# Motors.net
KiCad netlist of a schematic drawn in Altium Designer
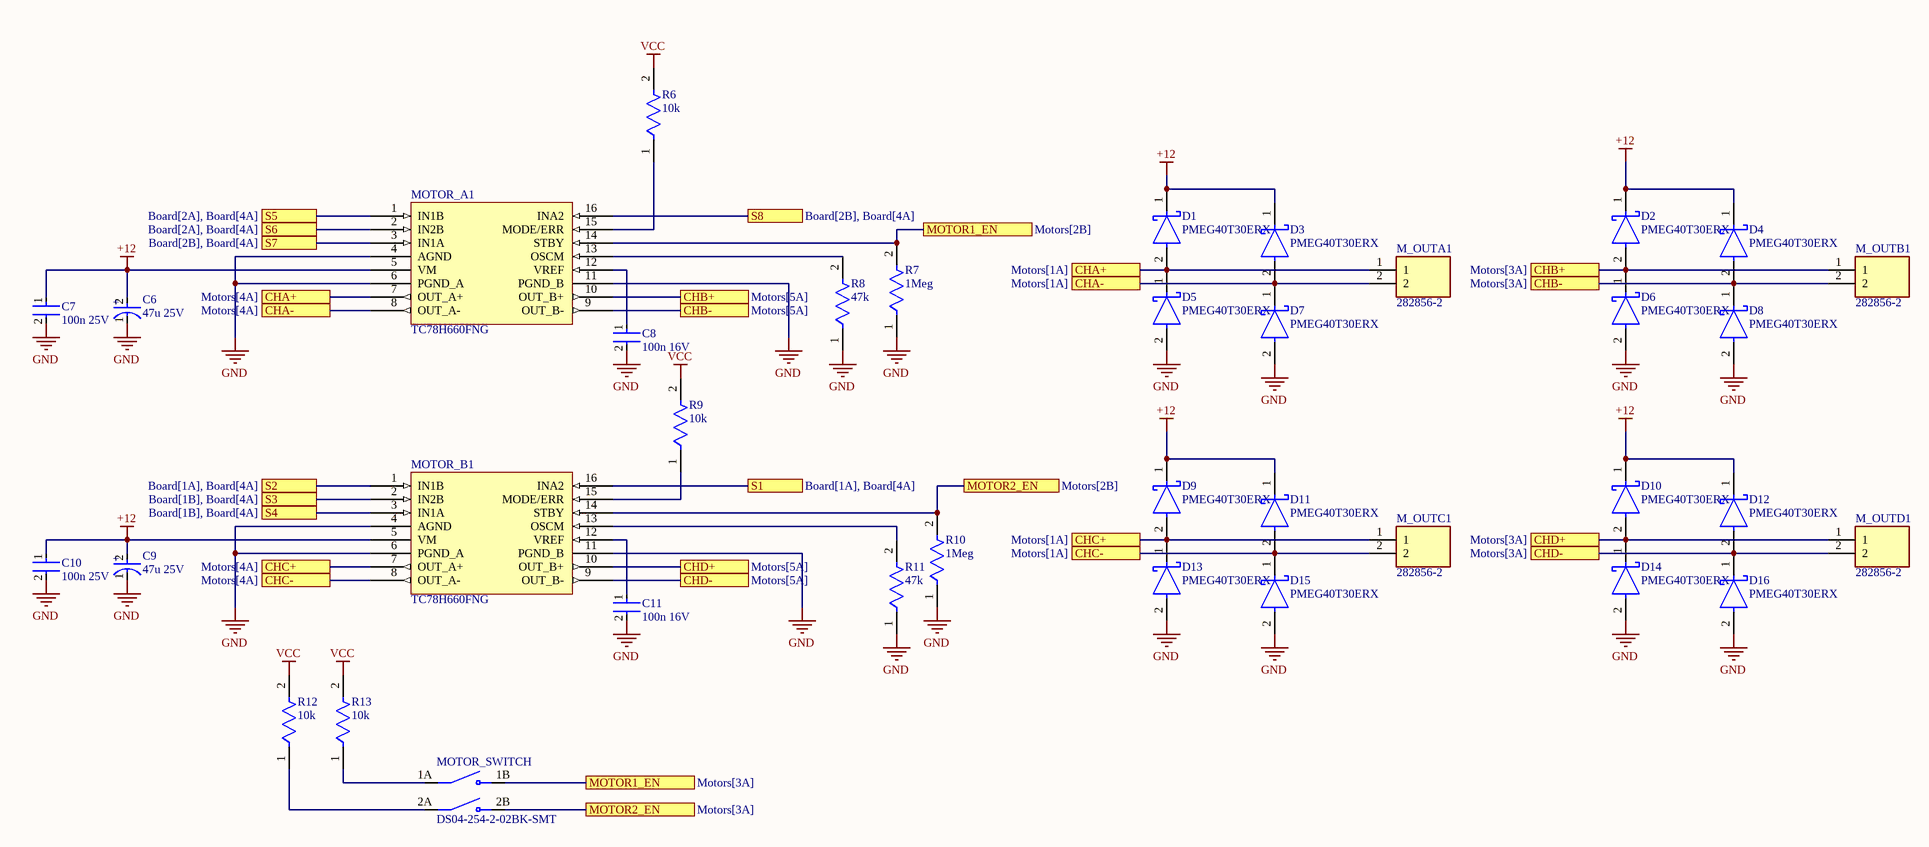
[diagram p0: Motors.SchDoc]

(export (version "E")
  (design (tool "Eeschema 10.0.6"))
  (components
    (comp (ref "C6")
      (value "47u 25V")
      (footprint "FP-T491D476K025AT-MFG")
      (description "CAP TANT 47UF 10% 25V 2917")
      (fields (field (name "VOLTAGE") "25V") (field (name "TOLERANCE") "10%"))
      (libsource (lib "Altium Content Vault") (part "203bc49f2ac43e59fd269a8c329ed05"))
    )
    (comp (ref "C7")
      (value "100n 25V")
      (footprint "FP-C0402-BB-MFG")
      (description "CAP CER 0.1UF 16V X7R 0402")
      (fields
        (field (name "TOLERANCE") "0.1")
        (field (name "OCTOPART") "https://octopart.com/c0402c104k4ractu-kemet-94158")
      )
      (libsource (lib "Altium Content Vault") (part "b4654b650e69147ec39a6b967a45e02"))
    )
    (comp (ref "C8")
      (value "100n 16V")
      (footprint "FP-C0402-BB-MFG")
      (description "CAP CER 0.1UF 16V X7R 0402")
      (fields
        (field (name "TOLERANCE") "0.1")
        (field (name "OCTOPART") "https://octopart.com/c0402c104k4ractu-kemet-94158")
      )
      (libsource (lib "Altium Content Vault") (part "b4654b650e69147ec39a6b967a45e02"))
    )
    (comp (ref "C9")
      (value "47u 25V")
      (footprint "FP-T491D476K025AT-MFG")
      (description "CAP TANT 47UF 10% 25V 2917")
      (fields (field (name "VOLTAGE") "25V") (field (name "TOLERANCE") "10%"))
      (libsource (lib "Altium Content Vault") (part "203bc49f2ac43e59fd269a8c329ed05"))
    )
    (comp (ref "C10")
      (value "100n 25V")
      (footprint "FP-C0402-BB-MFG")
      (description "CAP CER 0.1UF 16V X7R 0402")
      (fields
        (field (name "TOLERANCE") "0.1")
        (field (name "OCTOPART") "https://octopart.com/c0402c104k4ractu-kemet-94158")
      )
      (libsource (lib "Altium Content Vault") (part "b4654b650e69147ec39a6b967a45e02"))
    )
    (comp (ref "C11")
      (value "100n 16V")
      (footprint "FP-C0402-BB-MFG")
      (description "CAP CER 0.1UF 16V X7R 0402")
      (fields
        (field (name "TOLERANCE") "0.1")
        (field (name "OCTOPART") "https://octopart.com/c0402c104k4ractu-kemet-94158")
      )
      (libsource (lib "Altium Content Vault") (part "b4654b650e69147ec39a6b967a45e02"))
    )
    (comp (ref "D1")
      (value "PMEG40T30ERX")
      (footprint "FP-SOD123-IPC_A")
      (description "DIODE SCHOTTKY 40V 1A SOD123")
      (libsource (lib "Altium Content Vault") (part "1d6ec82d83fb6aee721767c19dac4b9"))
    )
    (comp (ref "D2")
      (value "PMEG40T30ERX")
      (footprint "FP-SOD123-IPC_A")
      (description "DIODE SCHOTTKY 40V 1A SOD123")
      (libsource (lib "Altium Content Vault") (part "1d6ec82d83fb6aee721767c19dac4b9"))
    )
    (comp (ref "D3")
      (value "PMEG40T30ERX")
      (footprint "FP-SOD123-IPC_A")
      (description "DIODE SCHOTTKY 40V 1A SOD123")
      (libsource (lib "Altium Content Vault") (part "1d6ec82d83fb6aee721767c19dac4b9"))
    )
    (comp (ref "D4")
      (value "PMEG40T30ERX")
      (footprint "FP-SOD123-IPC_A")
      (description "DIODE SCHOTTKY 40V 1A SOD123")
      (libsource (lib "Altium Content Vault") (part "1d6ec82d83fb6aee721767c19dac4b9"))
    )
    (comp (ref "D5")
      (value "PMEG40T30ERX")
      (footprint "FP-SOD123-IPC_A")
      (description "DIODE SCHOTTKY 40V 1A SOD123")
      (libsource (lib "Altium Content Vault") (part "1d6ec82d83fb6aee721767c19dac4b9"))
    )
    (comp (ref "D6")
      (value "PMEG40T30ERX")
      (footprint "FP-SOD123-IPC_A")
      (description "DIODE SCHOTTKY 40V 1A SOD123")
      (libsource (lib "Altium Content Vault") (part "1d6ec82d83fb6aee721767c19dac4b9"))
    )
    (comp (ref "D7")
      (value "PMEG40T30ERX")
      (footprint "FP-SOD123-IPC_A")
      (description "DIODE SCHOTTKY 40V 1A SOD123")
      (libsource (lib "Altium Content Vault") (part "1d6ec82d83fb6aee721767c19dac4b9"))
    )
    (comp (ref "D8")
      (value "PMEG40T30ERX")
      (footprint "FP-SOD123-IPC_A")
      (description "DIODE SCHOTTKY 40V 1A SOD123")
      (libsource (lib "Altium Content Vault") (part "1d6ec82d83fb6aee721767c19dac4b9"))
    )
    (comp (ref "D9")
      (value "PMEG40T30ERX")
      (footprint "FP-SOD123-IPC_A")
      (description "DIODE SCHOTTKY 40V 1A SOD123")
      (libsource (lib "Altium Content Vault") (part "1d6ec82d83fb6aee721767c19dac4b9"))
    )
    (comp (ref "D10")
      (value "PMEG40T30ERX")
      (footprint "FP-SOD123-IPC_A")
      (description "DIODE SCHOTTKY 40V 1A SOD123")
      (libsource (lib "Altium Content Vault") (part "1d6ec82d83fb6aee721767c19dac4b9"))
    )
    (comp (ref "D11")
      (value "PMEG40T30ERX")
      (footprint "FP-SOD123-IPC_A")
      (description "DIODE SCHOTTKY 40V 1A SOD123")
      (libsource (lib "Altium Content Vault") (part "1d6ec82d83fb6aee721767c19dac4b9"))
    )
    (comp (ref "D12")
      (value "PMEG40T30ERX")
      (footprint "FP-SOD123-IPC_A")
      (description "DIODE SCHOTTKY 40V 1A SOD123")
      (libsource (lib "Altium Content Vault") (part "1d6ec82d83fb6aee721767c19dac4b9"))
    )
    (comp (ref "D13")
      (value "PMEG40T30ERX")
      (footprint "FP-SOD123-IPC_A")
      (description "DIODE SCHOTTKY 40V 1A SOD123")
      (libsource (lib "Altium Content Vault") (part "1d6ec82d83fb6aee721767c19dac4b9"))
    )
    (comp (ref "D14")
      (value "PMEG40T30ERX")
      (footprint "FP-SOD123-IPC_A")
      (description "DIODE SCHOTTKY 40V 1A SOD123")
      (libsource (lib "Altium Content Vault") (part "1d6ec82d83fb6aee721767c19dac4b9"))
    )
    (comp (ref "D15")
      (value "PMEG40T30ERX")
      (footprint "FP-SOD123-IPC_A")
      (description "DIODE SCHOTTKY 40V 1A SOD123")
      (libsource (lib "Altium Content Vault") (part "1d6ec82d83fb6aee721767c19dac4b9"))
    )
    (comp (ref "D16")
      (value "PMEG40T30ERX")
      (footprint "FP-SOD123-IPC_A")
      (description "DIODE SCHOTTKY 40V 1A SOD123")
      (libsource (lib "Altium Content Vault") (part "1d6ec82d83fb6aee721767c19dac4b9"))
    )
    (comp (ref "MOTOR_A1")
      (value "TC78H660FNG")
      (footprint "TSOP65P640X120-16N")
      (description "Toshiba two channel dc motor driver , 2A for each channel.")
      (libsource (lib "Politechnika Wrocławska") (part "New symbol 1"))
    )
    (comp (ref "MOTOR_B1")
      (value "TC78H660FNG")
      (footprint "TSOP65P640X120-16N")
      (description "Toshiba two channel dc motor driver , 2A for each channel.")
      (libsource (lib "Politechnika Wrocławska") (part "New symbol 1"))
    )
    (comp (ref "MOTOR_SWITCH")
      (value "DS04-254-2-02BK-SMT")
      (footprint "SW_DS04-254-2-02BK-SMT")
      (description "2 Position, Surface Mount, 2.54 mm Pitch, Flat Slide Actuator, Flat Bottom, SMT Pin, DIP Switch")
      (fields
        (field (name "MF") "CUI Devices")
        (field (name "DIGI-KEY_PART_NUMBER") "2223-DS04-254-2-02BK-SMT-ND")
      )
      (libsource (lib "Politechnika Wrocławska") (part "DS04-254-2-02BK-SMT"))
    )
    (comp (ref "M_OUTA1")
      (value "282856-2")
      (footprint "TE_282856-2")
      (description "TERMI-BLOK PCB MOUNT 2P")
      (fields (field (name "MF") "TE Connectivity") (field (name "DIGI-KEY_PART_NUMBER") "A98108-ND"))
      (libsource (lib "Politechnika Wrocławska") (part "282856-2"))
    )
    (comp (ref "M_OUTB1")
      (value "282856-2")
      (footprint "TE_282856-2")
      (description "TERMI-BLOK PCB MOUNT 2P")
      (fields (field (name "MF") "TE Connectivity") (field (name "DIGI-KEY_PART_NUMBER") "A98108-ND"))
      (libsource (lib "Politechnika Wrocławska") (part "282856-2"))
    )
    (comp (ref "M_OUTC1")
      (value "282856-2")
      (footprint "TE_282856-2")
      (description "TERMI-BLOK PCB MOUNT 2P")
      (fields (field (name "MF") "TE Connectivity") (field (name "DIGI-KEY_PART_NUMBER") "A98108-ND"))
      (libsource (lib "Politechnika Wrocławska") (part "282856-2"))
    )
    (comp (ref "M_OUTD1")
      (value "282856-2")
      (footprint "TE_282856-2")
      (description "TERMI-BLOK PCB MOUNT 2P")
      (fields (field (name "MF") "TE Connectivity") (field (name "DIGI-KEY_PART_NUMBER") "A98108-ND"))
      (libsource (lib "Politechnika Wrocławska") (part "282856-2"))
    )
    (comp (ref "R6")
      (value "10k")
      (footprint "FP-CRCW0402-e3-IPC_C")
      (description "RES Thick Film, 0Ω, 0.063W, 0402")
      (fields (field (name "TOLERANCE") "5%"))
      (libsource (lib "Altium Content Vault") (part "1029c3af85768c4190bb7ad29bc67b5"))
    )
    (comp (ref "R7")
      (value "1Meg")
      (footprint "FP-CRCW0402-e3-IPC_C")
      (description "RES Thick Film, 0Ω, 0.063W, 0402")
      (fields (field (name "TOLERANCE") "5%"))
      (libsource (lib "Altium Content Vault") (part "1029c3af85768c4190bb7ad29bc67b5"))
    )
    (comp (ref "R8")
      (value "47k")
      (footprint "FP-CRCW0402-e3-IPC_C")
      (description "RES Thick Film, 0Ω, 0.063W, 0402")
      (fields (field (name "TOLERANCE") "5%"))
      (libsource (lib "Altium Content Vault") (part "1029c3af85768c4190bb7ad29bc67b5"))
    )
    (comp (ref "R9")
      (value "10k")
      (footprint "FP-CRCW0402-e3-IPC_C")
      (description "RES Thick Film, 0Ω, 0.063W, 0402")
      (fields (field (name "TOLERANCE") "5%"))
      (libsource (lib "Altium Content Vault") (part "1029c3af85768c4190bb7ad29bc67b5"))
    )
    (comp (ref "R10")
      (value "1Meg")
      (footprint "FP-CRCW0402-e3-IPC_C")
      (description "RES Thick Film, 0Ω, 0.063W, 0402")
      (fields (field (name "TOLERANCE") "5%"))
      (libsource (lib "Altium Content Vault") (part "1029c3af85768c4190bb7ad29bc67b5"))
    )
    (comp (ref "R11")
      (value "47k")
      (footprint "FP-CRCW0402-e3-IPC_C")
      (description "RES Thick Film, 0Ω, 0.063W, 0402")
      (fields (field (name "TOLERANCE") "5%"))
      (libsource (lib "Altium Content Vault") (part "1029c3af85768c4190bb7ad29bc67b5"))
    )
    (comp (ref "R12")
      (value "10k")
      (footprint "FP-CRCW0402-e3-IPC_C")
      (description "RES Thick Film, 0Ω, 0.063W, 0402")
      (fields (field (name "TOLERANCE") "5%"))
      (libsource (lib "Altium Content Vault") (part "1029c3af85768c4190bb7ad29bc67b5"))
    )
    (comp (ref "R13")
      (value "10k")
      (footprint "FP-CRCW0402-e3-IPC_C")
      (description "RES Thick Film, 0Ω, 0.063W, 0402")
      (fields (field (name "TOLERANCE") "5%"))
      (libsource (lib "Altium Content Vault") (part "1029c3af85768c4190bb7ad29bc67b5"))
    )
  )
  (nets
    (net (code "1") (name "+12") (class "Default")
      (node (ref "C10") (pin "1") (pinfunction "1_1") (pintype "passive"))
      (node (ref "C6") (pin "2") (pinfunction "A_2") (pintype "passive"))
      (node (ref "C7") (pin "1") (pinfunction "1_1") (pintype "passive"))
      (node (ref "C9") (pin "2") (pinfunction "A_2") (pintype "passive"))
      (node (ref "D1") (pin "1") (pinfunction "C_1") (pintype "passive"))
      (node (ref "D10") (pin "1") (pinfunction "C_1") (pintype "passive"))
      (node (ref "D11") (pin "1") (pinfunction "C_1") (pintype "passive"))
      (node (ref "D12") (pin "1") (pinfunction "C_1") (pintype "passive"))
      (node (ref "D2") (pin "1") (pinfunction "C_1") (pintype "passive"))
      (node (ref "D3") (pin "1") (pinfunction "C_1") (pintype "passive"))
      (node (ref "D4") (pin "1") (pinfunction "C_1") (pintype "passive"))
      (node (ref "D9") (pin "1") (pinfunction "C_1") (pintype "passive"))
      (node (ref "MOTOR_A1") (pin "5") (pinfunction "VM_5") (pintype "power_in"))
      (node (ref "MOTOR_B1") (pin "5") (pinfunction "VM_5") (pintype "power_in"))
    )
    (net (code "2") (name "/CHA+") (class "Default")
      (node (ref "D1") (pin "2") (pinfunction "A_2") (pintype "passive"))
      (node (ref "D5") (pin "1") (pinfunction "C_1") (pintype "passive"))
      (node (ref "MOTOR_A1") (pin "7") (pinfunction "OUT_A+_7") (pintype "output"))
      (node (ref "M_OUTA1") (pin "1") (pinfunction "1_1") (pintype "passive"))
    )
    (net (code "3") (name "/CHA-") (class "Default")
      (node (ref "D3") (pin "2") (pinfunction "A_2") (pintype "passive"))
      (node (ref "D7") (pin "1") (pinfunction "C_1") (pintype "passive"))
      (node (ref "MOTOR_A1") (pin "8") (pinfunction "OUT_A-_8") (pintype "output"))
      (node (ref "M_OUTA1") (pin "2") (pinfunction "2_2") (pintype "passive"))
    )
    (net (code "4") (name "/CHB+") (class "Default")
      (node (ref "D2") (pin "2") (pinfunction "A_2") (pintype "passive"))
      (node (ref "D6") (pin "1") (pinfunction "C_1") (pintype "passive"))
      (node (ref "MOTOR_A1") (pin "10") (pinfunction "OUT_B+_10") (pintype "output"))
      (node (ref "M_OUTB1") (pin "1") (pinfunction "1_1") (pintype "passive"))
    )
    (net (code "5") (name "/CHB-") (class "Default")
      (node (ref "D4") (pin "2") (pinfunction "A_2") (pintype "passive"))
      (node (ref "D8") (pin "1") (pinfunction "C_1") (pintype "passive"))
      (node (ref "MOTOR_A1") (pin "9") (pinfunction "OUT_B-_9") (pintype "output"))
      (node (ref "M_OUTB1") (pin "2") (pinfunction "2_2") (pintype "passive"))
    )
    (net (code "6") (name "/CHC+") (class "Default")
      (node (ref "D13") (pin "1") (pinfunction "C_1") (pintype "passive"))
      (node (ref "D9") (pin "2") (pinfunction "A_2") (pintype "passive"))
      (node (ref "MOTOR_B1") (pin "7") (pinfunction "OUT_A+_7") (pintype "output"))
      (node (ref "M_OUTC1") (pin "1") (pinfunction "1_1") (pintype "passive"))
    )
    (net (code "7") (name "/CHC-") (class "Default")
      (node (ref "D11") (pin "2") (pinfunction "A_2") (pintype "passive"))
      (node (ref "D15") (pin "1") (pinfunction "C_1") (pintype "passive"))
      (node (ref "MOTOR_B1") (pin "8") (pinfunction "OUT_A-_8") (pintype "output"))
      (node (ref "M_OUTC1") (pin "2") (pinfunction "2_2") (pintype "passive"))
    )
    (net (code "8") (name "/CHD+") (class "Default")
      (node (ref "D10") (pin "2") (pinfunction "A_2") (pintype "passive"))
      (node (ref "D14") (pin "1") (pinfunction "C_1") (pintype "passive"))
      (node (ref "MOTOR_B1") (pin "10") (pinfunction "OUT_B+_10") (pintype "output"))
      (node (ref "M_OUTD1") (pin "1") (pinfunction "1_1") (pintype "passive"))
    )
    (net (code "9") (name "/CHD-") (class "Default")
      (node (ref "D12") (pin "2") (pinfunction "A_2") (pintype "passive"))
      (node (ref "D16") (pin "1") (pinfunction "C_1") (pintype "passive"))
      (node (ref "MOTOR_B1") (pin "9") (pinfunction "OUT_B-_9") (pintype "output"))
      (node (ref "M_OUTD1") (pin "2") (pinfunction "2_2") (pintype "passive"))
    )
    (net (code "10") (name "/MOTOR1_EN") (class "Default")
      (node (ref "MOTOR_A1") (pin "14") (pinfunction "STBY_14") (pintype "input"))
      (node (ref "MOTOR_SWITCH") (pin "1B") (pinfunction "NO1_1B") (pintype "passive"))
      (node (ref "R7") (pin "2") (pinfunction "2_2") (pintype "passive"))
    )
    (net (code "11") (name "/MOTOR2_EN") (class "Default")
      (node (ref "MOTOR_B1") (pin "14") (pinfunction "STBY_14") (pintype "input"))
      (node (ref "MOTOR_SWITCH") (pin "2B") (pinfunction "NO2_2B") (pintype "passive"))
      (node (ref "R10") (pin "2") (pinfunction "2_2") (pintype "passive"))
    )
    (net (code "12") (name "/S1") (class "Default")
      (node (ref "MOTOR_B1") (pin "16") (pinfunction "INA2_16") (pintype "input"))
    )
    (net (code "13") (name "/S2") (class "Default")
      (node (ref "MOTOR_B1") (pin "1") (pinfunction "IN1B_1") (pintype "input"))
    )
    (net (code "14") (name "/S3") (class "Default")
      (node (ref "MOTOR_B1") (pin "2") (pinfunction "IN2B_2") (pintype "input"))
    )
    (net (code "15") (name "/S4") (class "Default")
      (node (ref "MOTOR_B1") (pin "3") (pinfunction "IN1A_3") (pintype "input"))
    )
    (net (code "16") (name "/S5") (class "Default")
      (node (ref "MOTOR_A1") (pin "1") (pinfunction "IN1B_1") (pintype "input"))
    )
    (net (code "17") (name "/S6") (class "Default")
      (node (ref "MOTOR_A1") (pin "2") (pinfunction "IN2B_2") (pintype "input"))
    )
    (net (code "18") (name "/S7") (class "Default")
      (node (ref "MOTOR_A1") (pin "3") (pinfunction "IN1A_3") (pintype "input"))
    )
    (net (code "19") (name "/S8") (class "Default")
      (node (ref "MOTOR_A1") (pin "16") (pinfunction "INA2_16") (pintype "input"))
    )
    (net (code "20") (name "GND") (class "Default")
      (node (ref "C10") (pin "2") (pinfunction "2_2") (pintype "passive"))
      (node (ref "C11") (pin "2") (pinfunction "2_2") (pintype "passive"))
      (node (ref "C6") (pin "1") (pinfunction "C_1") (pintype "passive"))
      (node (ref "C7") (pin "2") (pinfunction "2_2") (pintype "passive"))
      (node (ref "C8") (pin "2") (pinfunction "2_2") (pintype "passive"))
      (node (ref "C9") (pin "1") (pinfunction "C_1") (pintype "passive"))
      (node (ref "D13") (pin "2") (pinfunction "A_2") (pintype "passive"))
      (node (ref "D14") (pin "2") (pinfunction "A_2") (pintype "passive"))
      (node (ref "D15") (pin "2") (pinfunction "A_2") (pintype "passive"))
      (node (ref "D16") (pin "2") (pinfunction "A_2") (pintype "passive"))
      (node (ref "D5") (pin "2") (pinfunction "A_2") (pintype "passive"))
      (node (ref "D6") (pin "2") (pinfunction "A_2") (pintype "passive"))
      (node (ref "D7") (pin "2") (pinfunction "A_2") (pintype "passive"))
      (node (ref "D8") (pin "2") (pinfunction "A_2") (pintype "passive"))
      (node (ref "MOTOR_A1") (pin "11") (pinfunction "PGND_B_11") (pintype "power_in"))
      (node (ref "MOTOR_A1") (pin "4") (pinfunction "AGND_4") (pintype "power_in"))
      (node (ref "MOTOR_A1") (pin "6") (pinfunction "PGND_A_6") (pintype "power_in"))
      (node (ref "MOTOR_B1") (pin "11") (pinfunction "PGND_B_11") (pintype "power_in"))
      (node (ref "MOTOR_B1") (pin "4") (pinfunction "AGND_4") (pintype "power_in"))
      (node (ref "MOTOR_B1") (pin "6") (pinfunction "PGND_A_6") (pintype "power_in"))
      (node (ref "R10") (pin "1") (pinfunction "1_1") (pintype "passive"))
      (node (ref "R11") (pin "1") (pinfunction "1_1") (pintype "passive"))
      (node (ref "R7") (pin "1") (pinfunction "1_1") (pintype "passive"))
      (node (ref "R8") (pin "1") (pinfunction "1_1") (pintype "passive"))
    )
    (net (code "21") (name "Net-(MOTOR_A1-MODE{slash}ERR)") (class "Default")
      (node (ref "MOTOR_A1") (pin "15") (pinfunction "MODE/ERR_15") (pintype "input"))
      (node (ref "R6") (pin "1") (pinfunction "1_1") (pintype "passive"))
    )
    (net (code "22") (name "Net-(MOTOR_A1-OSCM)") (class "Default")
      (node (ref "MOTOR_A1") (pin "13") (pinfunction "OSCM_13") (pintype "input"))
      (node (ref "R8") (pin "2") (pinfunction "2_2") (pintype "passive"))
    )
    (net (code "23") (name "Net-(MOTOR_A1-VREF)") (class "Default")
      (node (ref "C8") (pin "1") (pinfunction "1_1") (pintype "passive"))
      (node (ref "MOTOR_A1") (pin "12") (pinfunction "VREF_12") (pintype "input"))
    )
    (net (code "24") (name "Net-(MOTOR_B1-MODE{slash}ERR)") (class "Default")
      (node (ref "MOTOR_B1") (pin "15") (pinfunction "MODE/ERR_15") (pintype "input"))
      (node (ref "R9") (pin "1") (pinfunction "1_1") (pintype "passive"))
    )
    (net (code "25") (name "Net-(MOTOR_B1-OSCM)") (class "Default")
      (node (ref "MOTOR_B1") (pin "13") (pinfunction "OSCM_13") (pintype "input"))
      (node (ref "R11") (pin "2") (pinfunction "2_2") (pintype "passive"))
    )
    (net (code "26") (name "Net-(MOTOR_B1-VREF)") (class "Default")
      (node (ref "C11") (pin "1") (pinfunction "1_1") (pintype "passive"))
      (node (ref "MOTOR_B1") (pin "12") (pinfunction "VREF_12") (pintype "input"))
    )
    (net (code "27") (name "Net-(MOTOR_SWITCH-COM1)") (class "Default")
      (node (ref "MOTOR_SWITCH") (pin "1A") (pinfunction "COM1_1A") (pintype "passive"))
      (node (ref "R13") (pin "1") (pinfunction "1_1") (pintype "passive"))
    )
    (net (code "28") (name "Net-(MOTOR_SWITCH-COM2)") (class "Default")
      (node (ref "MOTOR_SWITCH") (pin "2A") (pinfunction "COM2_2A") (pintype "passive"))
      (node (ref "R12") (pin "1") (pinfunction "1_1") (pintype "passive"))
    )
    (net (code "29") (name "VCC") (class "Default")
      (node (ref "R12") (pin "2") (pinfunction "2_2") (pintype "passive"))
      (node (ref "R13") (pin "2") (pinfunction "2_2") (pintype "passive"))
      (node (ref "R6") (pin "2") (pinfunction "2_2") (pintype "passive"))
      (node (ref "R9") (pin "2") (pinfunction "2_2") (pintype "passive"))
    )
  )
)
